# ledstringpower.net
KiCad netlist of a schematic drawn in EAGLE
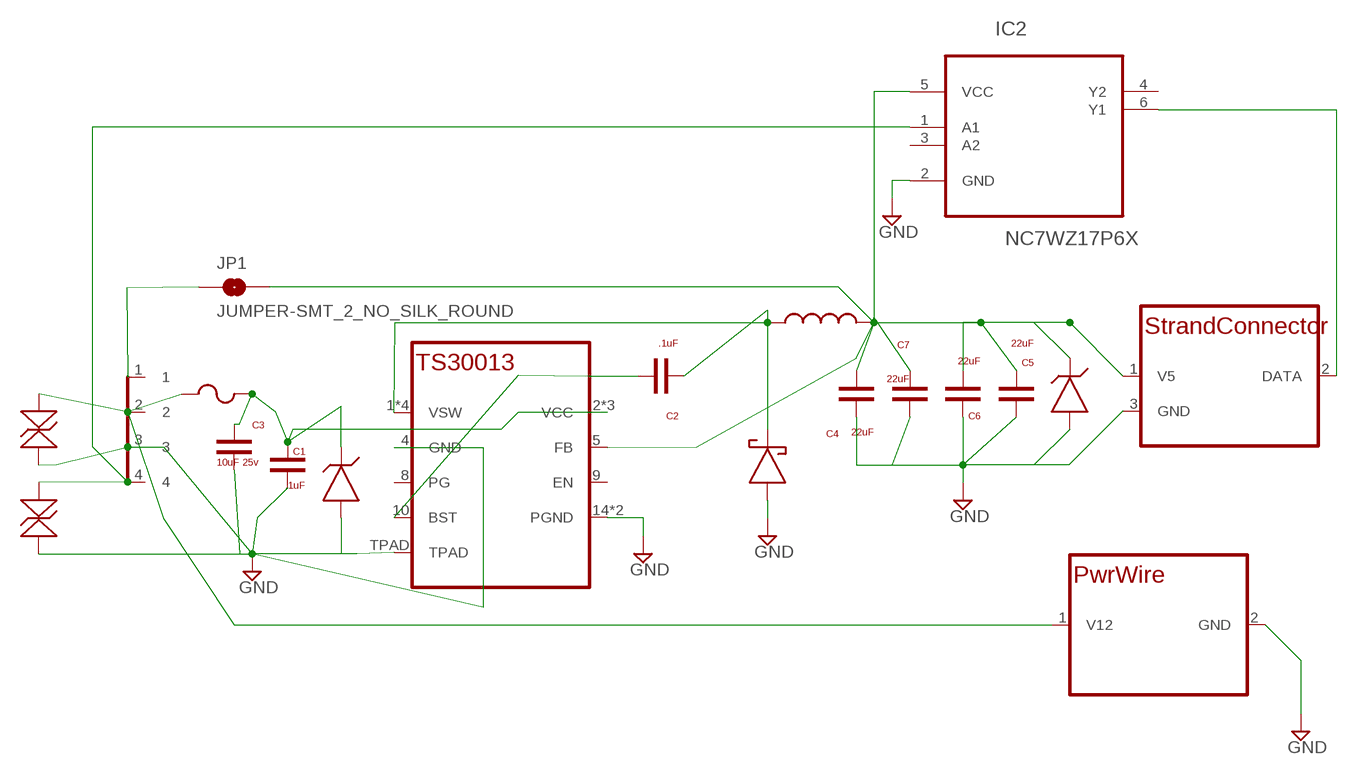
[diagram p0: schematic, sheet 1]

(export (version "E")
  (design (tool "Eeschema 10.0.6"))
  (components
    (comp (ref "C1")
      (value ".1uF")
      (footprint "eagle-import:C0603")
      (libsource (lib "eagle-import") (part "CAPACITOR_NONPOLARC0603"))
    )
    (comp (ref "C2")
      (value ".1uF")
      (footprint "eagle-import:C0603")
      (libsource (lib "eagle-import") (part "CAPACITOR_NONPOLARC0603"))
    )
    (comp (ref "C3")
      (value "10uF 25v")
      (footprint "eagle-import:C1206")
      (libsource (lib "eagle-import") (part "CL31A106MAHNNNEC1206"))
    )
    (comp (ref "C4")
      (value "22uF")
      (footprint "eagle-import:C0603")
      (libsource (lib "eagle-import") (part "GRM188R61A226ME15DC0603"))
    )
    (comp (ref "C5")
      (value "22uF")
      (footprint "eagle-import:C0603")
      (libsource (lib "eagle-import") (part "GRM188R61A226ME15DC0603"))
    )
    (comp (ref "C6")
      (value "22uF")
      (footprint "eagle-import:C0603")
      (libsource (lib "eagle-import") (part "GRM188R61A226ME15DC0603"))
    )
    (comp (ref "C7")
      (value "22uF")
      (footprint "eagle-import:C0603")
      (libsource (lib "eagle-import") (part "GRM188R61A226ME15DC0603"))
    )
    (comp (ref "D2")
      (value "LS54LS54")
      (footprint "eagle-import:LS54")
      (libsource (lib "eagle-import") (part "LS54LS54"))
    )
    (comp (ref "F1")
      (value "3A")
      (footprint "eagle-import:R0603")
      (libsource (lib "eagle-import") (part "FUSER0603"))
    )
    (comp (ref "IC1")
      (value "TS30013QFN16-3X3-DIY")
      (footprint "eagle-import:QFN16-3X3-DIY")
      (libsource (lib "eagle-import") (part "TS30013QFN16-3X3-DIY"))
    )
    (comp (ref "IC2")
      (value "NC7WZ17P6X")
      (footprint "eagle-import:SOT65P210X110-6N")
      (libsource (lib "eagle-import") (part "NC7WZ17P6X"))
    )
    (comp (ref "JP1")
      (value "JUMPER-SMT_2_NO_SILK_ROUND")
      (footprint "eagle-import:SMT-JUMPER_2_NO_SILK_ROUND")
      (libsource (lib "eagle-import") (part "JUMPER-SMT_2_NO_SILK_ROUND"))
    )
    (comp (ref "L1")
      (value "SRN5040TA-4R7MSRN5040TA")
      (footprint "eagle-import:SRN5040TA")
      (libsource (lib "eagle-import") (part "SRN5040TA-4R7MSRN5040TA"))
    )
    (comp (ref "TVS1")
      (value "DESD5V0U1BL-7BDFN1006-2")
      (footprint "eagle-import:DFN1006-2")
      (libsource (lib "eagle-import") (part "DESD5V0U1BL-7BDFN1006-2"))
    )
    (comp (ref "TVS2")
      (value "DESD5V0U1BL-7BDFN1006-2")
      (footprint "eagle-import:DFN1006-2")
      (libsource (lib "eagle-import") (part "DESD5V0U1BL-7BDFN1006-2"))
    )
    (comp (ref "U$3")
      (value "TE-1969806-1TE-1969806-1")
      (footprint "eagle-import:TE-1969806-1")
      (libsource (lib "eagle-import") (part "TE-1969806-1TE-1969806-1"))
    )
    (comp (ref "U$5")
      (value "LEDSTRANDDLEDWIREP")
      (footprint "eagle-import:LEDWIREP")
      (libsource (lib "eagle-import") (part "LEDSTRANDDLEDWIREP"))
    )
    (comp (ref "U$8")
      (value "PWRWIREDPWRWIREP")
      (footprint "eagle-import:PWRWIREP")
      (libsource (lib "eagle-import") (part "PWRWIREDPWRWIREP"))
    )
    (comp (ref "Z1")
      (value "1SMB5930BT3G1SMB5930BT3G")
      (footprint "eagle-import:1SMB5930BT3G")
      (libsource (lib "eagle-import") (part "1SMB5930BT3G1SMB5930BT3G"))
    )
    (comp (ref "Z2")
      (value "MMSZ5231BT3G-5V1-ZENERSOD123")
      (footprint "eagle-import:SOD123")
      (libsource (lib "eagle-import") (part "MMSZ5231BT3G-5V1-ZENERSOD123"))
    )
  )
  (nets
    (net (code "1") (name "GND") (class "Default")
      (node (ref "C1") (pin "1") (pinfunction "1_1") (pintype "bidirectional"))
      (node (ref "C3") (pin "2") (pinfunction "2_2") (pintype "bidirectional"))
      (node (ref "C4") (pin "1") (pinfunction "1_1") (pintype "bidirectional"))
      (node (ref "C5") (pin "1") (pinfunction "1_1") (pintype "bidirectional"))
      (node (ref "C6") (pin "1") (pinfunction "1_1") (pintype "bidirectional"))
      (node (ref "C7") (pin "1") (pinfunction "1_1") (pintype "bidirectional"))
      (node (ref "D2") (pin "1") (pinfunction "1_1") (pintype "bidirectional"))
      (node (ref "IC1") (pin "14") (pinfunction "PGND_14") (pintype "bidirectional"))
      (node (ref "IC1") (pin "15") (pinfunction "PGND_15") (pintype "bidirectional"))
      (node (ref "IC1") (pin "4") (pinfunction "GND_4") (pintype "bidirectional"))
      (node (ref "IC1") (pin "TPAD") (pinfunction "TPAD_TPAD") (pintype "bidirectional"))
      (node (ref "IC2") (pin "2") (pinfunction "GND_2") (pintype "passive"))
      (node (ref "TVS1") (pin "1") (pinfunction "1_1") (pintype "bidirectional"))
      (node (ref "TVS2") (pin "1") (pinfunction "1_1") (pintype "bidirectional"))
      (node (ref "U$3") (pin "3") (pinfunction "3_3") (pintype "bidirectional"))
      (node (ref "U$5") (pin "3") (pinfunction "GND_3") (pintype "bidirectional"))
      (node (ref "U$8") (pin "2") (pinfunction "GND_2") (pintype "bidirectional"))
      (node (ref "Z1") (pin "1") (pinfunction "1_1") (pintype "bidirectional"))
      (node (ref "Z2") (pin "1") (pinfunction "1_1") (pintype "bidirectional"))
    )
    (net (code "2") (name "Net-(C1-Pad2)") (class "Default")
      (node (ref "C1") (pin "2") (pinfunction "2_2") (pintype "bidirectional"))
      (node (ref "C3") (pin "1") (pinfunction "1_1") (pintype "bidirectional"))
      (node (ref "F1") (pin "2") (pinfunction "2_2") (pintype "bidirectional"))
      (node (ref "IC1") (pin "11") (pinfunction "VCC_11") (pintype "bidirectional"))
      (node (ref "IC1") (pin "2") (pinfunction "VCC_2") (pintype "bidirectional"))
      (node (ref "IC1") (pin "3") (pinfunction "VCC_3") (pintype "bidirectional"))
      (node (ref "Z1") (pin "2") (pinfunction "2_2") (pintype "bidirectional"))
    )
    (net (code "3") (name "Net-(C2-Pad1)") (class "Default")
      (node (ref "C2") (pin "1") (pinfunction "1_1") (pintype "bidirectional"))
      (node (ref "D2") (pin "2") (pinfunction "2_2") (pintype "bidirectional"))
      (node (ref "IC1") (pin "1") (pinfunction "VSW_1") (pintype "bidirectional"))
      (node (ref "IC1") (pin "12") (pinfunction "VSW_12") (pintype "bidirectional"))
      (node (ref "IC1") (pin "13") (pinfunction "VSW_13") (pintype "bidirectional"))
      (node (ref "IC1") (pin "16") (pinfunction "VSW_16") (pintype "bidirectional"))
      (node (ref "L1") (pin "1") (pinfunction "1_1") (pintype "bidirectional"))
    )
    (net (code "4") (name "Net-(IC1-BST)") (class "Default")
      (node (ref "C2") (pin "2") (pinfunction "2_2") (pintype "bidirectional"))
      (node (ref "IC1") (pin "10") (pinfunction "BST_10") (pintype "bidirectional"))
    )
    (net (code "5") (name "Net-(IC1-FB)") (class "Default")
      (node (ref "C4") (pin "2") (pinfunction "2_2") (pintype "bidirectional"))
      (node (ref "C5") (pin "2") (pinfunction "2_2") (pintype "bidirectional"))
      (node (ref "C6") (pin "2") (pinfunction "2_2") (pintype "bidirectional"))
      (node (ref "C7") (pin "2") (pinfunction "2_2") (pintype "bidirectional"))
      (node (ref "IC1") (pin "5") (pinfunction "FB_5") (pintype "bidirectional"))
      (node (ref "IC2") (pin "5") (pinfunction "VCC_5") (pintype "power_in"))
      (node (ref "JP1") (pin "2") (pinfunction "2_2") (pintype "passive"))
      (node (ref "L1") (pin "2") (pinfunction "2_2") (pintype "bidirectional"))
      (node (ref "U$5") (pin "1") (pinfunction "V5_1") (pintype "bidirectional"))
      (node (ref "Z2") (pin "2") (pinfunction "2_2") (pintype "bidirectional"))
    )
    (net (code "6") (name "Net-(IC2-A1)") (class "Default")
      (node (ref "IC2") (pin "1") (pinfunction "A1_1") (pintype "input"))
      (node (ref "TVS2") (pin "2") (pinfunction "2_2") (pintype "bidirectional"))
      (node (ref "U$3") (pin "4") (pinfunction "4_4") (pintype "bidirectional"))
    )
    (net (code "7") (name "Net-(IC2-Y1)") (class "Default")
      (node (ref "IC2") (pin "6") (pinfunction "Y1_6") (pintype "output"))
      (node (ref "U$5") (pin "2") (pinfunction "DATA_2") (pintype "bidirectional"))
    )
    (net (code "8") (name "Net-(JP1-Pad1)") (class "Default")
      (node (ref "JP1") (pin "1") (pinfunction "1_1") (pintype "passive"))
      (node (ref "U$3") (pin "1") (pinfunction "1_1") (pintype "bidirectional"))
    )
    (net (code "9") (name "Net-(U$8-V12)") (class "Default")
      (node (ref "F1") (pin "1") (pinfunction "1_1") (pintype "bidirectional"))
      (node (ref "TVS1") (pin "2") (pinfunction "2_2") (pintype "bidirectional"))
      (node (ref "U$3") (pin "2") (pinfunction "2_2") (pintype "bidirectional"))
      (node (ref "U$8") (pin "1") (pinfunction "V12_1") (pintype "bidirectional"))
    )
    (net (code "10") (name "unconnected-(IC1-EN-Pad9)") (class "Default")
      (node (ref "IC1") (pin "9") (pinfunction "EN_9") (pintype "bidirectional"))
    )
    (net (code "11") (name "unconnected-(IC1-PG-Pad8)") (class "Default")
      (node (ref "IC1") (pin "8") (pinfunction "PG_8") (pintype "bidirectional"))
    )
    (net (code "12") (name "unconnected-(IC2-A2-Pad3)") (class "Default")
      (node (ref "IC2") (pin "3") (pinfunction "A2_3") (pintype "input"))
    )
    (net (code "13") (name "unconnected-(IC2-Y2-Pad4)") (class "Default")
      (node (ref "IC2") (pin "4") (pinfunction "Y2_4") (pintype "output"))
    )
  )
)
